# 2-R2_Dac.net
KiCad netlist of a schematic drawn in Altium Designer
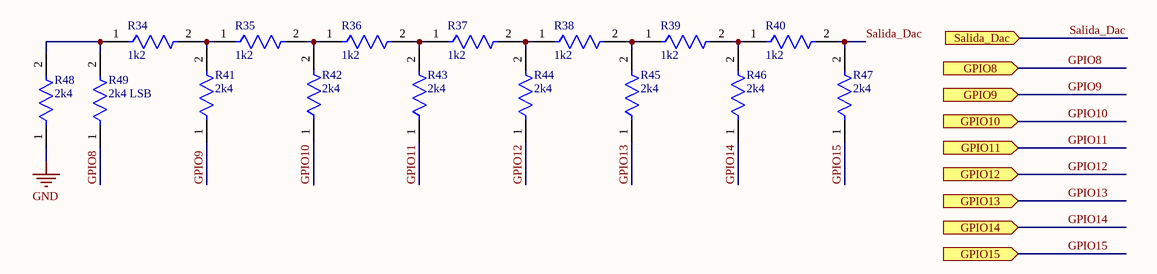
[diagram p0: 2-R2 Dac.SchDoc]

(export (version "E")
  (design (tool "Eeschema 10.0.6"))
  (components
    (comp (ref "R34")
      (value "1k2")
      (footprint "FP-MFR-25-MFG")
      (description "1.18 kOhms ±1% 0.25W, 1/4W Through Hole Resistor Axial  Metal Film")
      (fields (field (name "MANUFACTURER") "Yageo"))
      (libsource (lib "Altium Content Vault") (part "1029c3af85768c4190bb7ad29bc67b5"))
    )
    (comp (ref "R35")
      (value "1k2")
      (footprint "FP-MFR-25-MFG")
      (description "1.18 kOhms ±1% 0.25W, 1/4W Through Hole Resistor Axial  Metal Film")
      (fields (field (name "MANUFACTURER") "Yageo"))
      (libsource (lib "Altium Content Vault") (part "1029c3af85768c4190bb7ad29bc67b5"))
    )
    (comp (ref "R36")
      (value "1k2")
      (footprint "FP-MFR-25-MFG")
      (description "1.18 kOhms ±1% 0.25W, 1/4W Through Hole Resistor Axial  Metal Film")
      (fields (field (name "MANUFACTURER") "Yageo"))
      (libsource (lib "Altium Content Vault") (part "1029c3af85768c4190bb7ad29bc67b5"))
    )
    (comp (ref "R37")
      (value "1k2")
      (footprint "FP-MFR-25-MFG")
      (description "1.18 kOhms ±1% 0.25W, 1/4W Through Hole Resistor Axial  Metal Film")
      (fields (field (name "MANUFACTURER") "Yageo"))
      (libsource (lib "Altium Content Vault") (part "1029c3af85768c4190bb7ad29bc67b5"))
    )
    (comp (ref "R38")
      (value "1k2")
      (footprint "FP-MFR-25-MFG")
      (description "1.18 kOhms ±1% 0.25W, 1/4W Through Hole Resistor Axial  Metal Film")
      (fields (field (name "MANUFACTURER") "Yageo"))
      (libsource (lib "Altium Content Vault") (part "1029c3af85768c4190bb7ad29bc67b5"))
    )
    (comp (ref "R39")
      (value "1k2")
      (footprint "FP-MFR-25-MFG")
      (description "1.18 kOhms ±1% 0.25W, 1/4W Through Hole Resistor Axial  Metal Film")
      (fields (field (name "MANUFACTURER") "Yageo"))
      (libsource (lib "Altium Content Vault") (part "1029c3af85768c4190bb7ad29bc67b5"))
    )
    (comp (ref "R40")
      (value "1k2")
      (footprint "FP-MFR-25-MFG")
      (description "1.18 kOhms ±1% 0.25W, 1/4W Through Hole Resistor Axial  Metal Film")
      (fields (field (name "MANUFACTURER") "Yageo"))
      (libsource (lib "Altium Content Vault") (part "1029c3af85768c4190bb7ad29bc67b5"))
    )
    (comp (ref "R41")
      (value "2k4")
      (footprint "FP-MFR-25-MFG")
      (description "1.18 kOhms ±1% 0.25W, 1/4W Through Hole Resistor Axial  Metal Film")
      (fields (field (name "MANUFACTURER") "Yageo"))
      (libsource (lib "Altium Content Vault") (part "1029c3af85768c4190bb7ad29bc67b5"))
    )
    (comp (ref "R42")
      (value "2k4")
      (footprint "FP-MFR-25-MFG")
      (description "1.18 kOhms ±1% 0.25W, 1/4W Through Hole Resistor Axial  Metal Film")
      (fields (field (name "MANUFACTURER") "Yageo"))
      (libsource (lib "Altium Content Vault") (part "1029c3af85768c4190bb7ad29bc67b5"))
    )
    (comp (ref "R43")
      (value "2k4")
      (footprint "FP-MFR-25-MFG")
      (description "1.18 kOhms ±1% 0.25W, 1/4W Through Hole Resistor Axial  Metal Film")
      (fields (field (name "MANUFACTURER") "Yageo"))
      (libsource (lib "Altium Content Vault") (part "1029c3af85768c4190bb7ad29bc67b5"))
    )
    (comp (ref "R44")
      (value "2k4")
      (footprint "FP-MFR-25-MFG")
      (description "1.18 kOhms ±1% 0.25W, 1/4W Through Hole Resistor Axial  Metal Film")
      (fields (field (name "MANUFACTURER") "Yageo"))
      (libsource (lib "Altium Content Vault") (part "1029c3af85768c4190bb7ad29bc67b5"))
    )
    (comp (ref "R45")
      (value "2k4")
      (footprint "FP-MFR-25-MFG")
      (description "1.18 kOhms ±1% 0.25W, 1/4W Through Hole Resistor Axial  Metal Film")
      (fields (field (name "MANUFACTURER") "Yageo"))
      (libsource (lib "Altium Content Vault") (part "1029c3af85768c4190bb7ad29bc67b5"))
    )
    (comp (ref "R46")
      (value "2k4")
      (footprint "FP-MFR-25-MFG")
      (description "1.18 kOhms ±1% 0.25W, 1/4W Through Hole Resistor Axial  Metal Film")
      (fields (field (name "MANUFACTURER") "Yageo"))
      (libsource (lib "Altium Content Vault") (part "1029c3af85768c4190bb7ad29bc67b5"))
    )
    (comp (ref "R47")
      (value "2k4")
      (footprint "FP-MFR-25-MFG")
      (description "1.18 kOhms ±1% 0.25W, 1/4W Through Hole Resistor Axial  Metal Film")
      (fields (field (name "MANUFACTURER") "Yageo"))
      (libsource (lib "Altium Content Vault") (part "1029c3af85768c4190bb7ad29bc67b5"))
    )
    (comp (ref "R48")
      (value "2k4")
      (footprint "FP-MFR-25-MFG")
      (description "1.18 kOhms ±1% 0.25W, 1/4W Through Hole Resistor Axial  Metal Film")
      (fields (field (name "MANUFACTURER") "Yageo"))
      (libsource (lib "Altium Content Vault") (part "1029c3af85768c4190bb7ad29bc67b5"))
    )
    (comp (ref "R49")
      (value "2k4 LSB")
      (footprint "FP-MFR-25-MFG")
      (description "1.18 kOhms ±1% 0.25W, 1/4W Through Hole Resistor Axial  Metal Film")
      (fields (field (name "MANUFACTURER") "Yageo"))
      (libsource (lib "Altium Content Vault") (part "1029c3af85768c4190bb7ad29bc67b5"))
    )
  )
  (nets
    (net (code "1") (name "/GPIO8") (class "Default")
      (node (ref "R49") (pin "1") (pinfunction "1_1") (pintype "passive"))
    )
    (net (code "2") (name "/GPIO9") (class "Default")
      (node (ref "R41") (pin "1") (pinfunction "1_1") (pintype "passive"))
    )
    (net (code "3") (name "/GPIO10") (class "Default")
      (node (ref "R42") (pin "1") (pinfunction "1_1") (pintype "passive"))
    )
    (net (code "4") (name "/GPIO11") (class "Default")
      (node (ref "R43") (pin "1") (pinfunction "1_1") (pintype "passive"))
    )
    (net (code "5") (name "/GPIO12") (class "Default")
      (node (ref "R44") (pin "1") (pinfunction "1_1") (pintype "passive"))
    )
    (net (code "6") (name "/GPIO13") (class "Default")
      (node (ref "R45") (pin "1") (pinfunction "1_1") (pintype "passive"))
    )
    (net (code "7") (name "/GPIO14") (class "Default")
      (node (ref "R46") (pin "1") (pinfunction "1_1") (pintype "passive"))
    )
    (net (code "8") (name "/GPIO15") (class "Default")
      (node (ref "R47") (pin "1") (pinfunction "1_1") (pintype "passive"))
    )
    (net (code "9") (name "/Salida_Dac") (class "Default")
      (node (ref "R40") (pin "2") (pinfunction "2_2") (pintype "passive"))
      (node (ref "R47") (pin "2") (pinfunction "2_2") (pintype "passive"))
    )
    (net (code "10") (name "GND") (class "Default")
      (node (ref "R48") (pin "1") (pinfunction "1_1") (pintype "passive"))
    )
    (net (code "11") (name "Net-(R34-Pad1)") (class "Default")
      (node (ref "R34") (pin "1") (pinfunction "1_1") (pintype "passive"))
      (node (ref "R48") (pin "2") (pinfunction "2_2") (pintype "passive"))
      (node (ref "R49") (pin "2") (pinfunction "2_2") (pintype "passive"))
    )
    (net (code "12") (name "Net-(R34-Pad2)") (class "Default")
      (node (ref "R34") (pin "2") (pinfunction "2_2") (pintype "passive"))
      (node (ref "R35") (pin "1") (pinfunction "1_1") (pintype "passive"))
      (node (ref "R41") (pin "2") (pinfunction "2_2") (pintype "passive"))
    )
    (net (code "13") (name "Net-(R35-Pad2)") (class "Default")
      (node (ref "R35") (pin "2") (pinfunction "2_2") (pintype "passive"))
      (node (ref "R36") (pin "1") (pinfunction "1_1") (pintype "passive"))
      (node (ref "R42") (pin "2") (pinfunction "2_2") (pintype "passive"))
    )
    (net (code "14") (name "Net-(R36-Pad2)") (class "Default")
      (node (ref "R36") (pin "2") (pinfunction "2_2") (pintype "passive"))
      (node (ref "R37") (pin "1") (pinfunction "1_1") (pintype "passive"))
      (node (ref "R43") (pin "2") (pinfunction "2_2") (pintype "passive"))
    )
    (net (code "15") (name "Net-(R37-Pad2)") (class "Default")
      (node (ref "R37") (pin "2") (pinfunction "2_2") (pintype "passive"))
      (node (ref "R38") (pin "1") (pinfunction "1_1") (pintype "passive"))
      (node (ref "R44") (pin "2") (pinfunction "2_2") (pintype "passive"))
    )
    (net (code "16") (name "Net-(R38-Pad2)") (class "Default")
      (node (ref "R38") (pin "2") (pinfunction "2_2") (pintype "passive"))
      (node (ref "R39") (pin "1") (pinfunction "1_1") (pintype "passive"))
      (node (ref "R45") (pin "2") (pinfunction "2_2") (pintype "passive"))
    )
    (net (code "17") (name "Net-(R39-Pad2)") (class "Default")
      (node (ref "R39") (pin "2") (pinfunction "2_2") (pintype "passive"))
      (node (ref "R40") (pin "1") (pinfunction "1_1") (pintype "passive"))
      (node (ref "R46") (pin "2") (pinfunction "2_2") (pintype "passive"))
    )
  )
)
